# con-right-top.net
KiCad netlist of a schematic drawn in Altium Designer
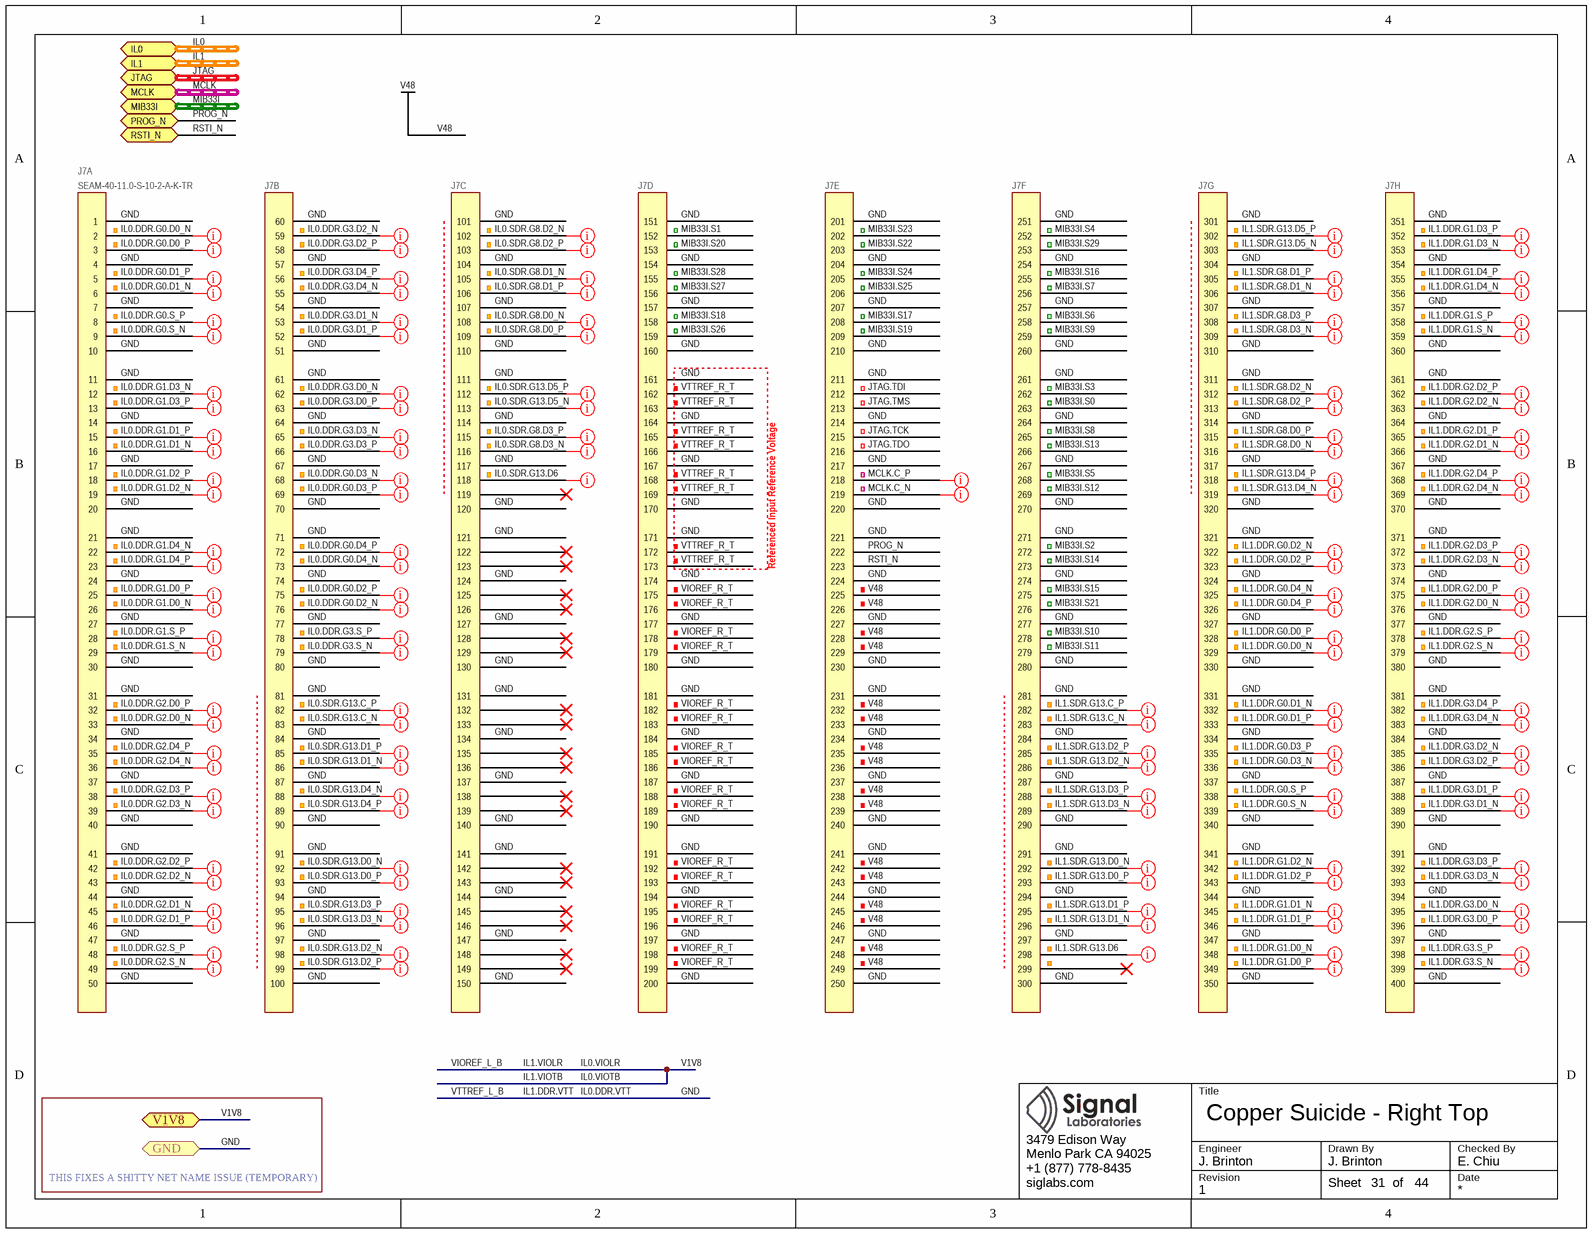
[diagram p0: con-right-top.SchDoc]

(export (version "E")
  (design (tool "Eeschema 10.0.6"))
  (components
    (comp (ref "J7")
      (value "SEAM-40-11.0-S-10-2-A-K-TR")
      (footprint "samtec:SEAM-40-11.0-S-10-2-A-K-TR")
      (description "Terminal Array Assembly, Surface Mount, 0.050\" Pitch, 400 Pins")
      (fields (field (name "MANUFACTURER") "Samtec"))
      (libsource (lib "samtec") (part "SEAM-40-11.0-S-10-2-A-K-TR"))
    )
  )
  (nets
    (net (code "6") (name "/GND") (class "Default")
      (node (ref "J7") (pin "1") (pinfunction "1_1") (pintype "passive"))
      (node (ref "J7") (pin "10") (pinfunction "10_10") (pintype "passive"))
      (node (ref "J7") (pin "100") (pinfunction "100_100") (pintype "passive"))
      (node (ref "J7") (pin "101") (pinfunction "101_101") (pintype "passive"))
      (node (ref "J7") (pin "104") (pinfunction "104_104") (pintype "passive"))
      (node (ref "J7") (pin "107") (pinfunction "107_107") (pintype "passive"))
      (node (ref "J7") (pin "11") (pinfunction "11_11") (pintype "passive"))
      (node (ref "J7") (pin "110") (pinfunction "110_110") (pintype "passive"))
      (node (ref "J7") (pin "111") (pinfunction "111_111") (pintype "passive"))
      (node (ref "J7") (pin "114") (pinfunction "114_114") (pintype "passive"))
      (node (ref "J7") (pin "117") (pinfunction "117_117") (pintype "passive"))
      (node (ref "J7") (pin "120") (pinfunction "120_120") (pintype "passive"))
      (node (ref "J7") (pin "121") (pinfunction "121_121") (pintype "passive"))
      (node (ref "J7") (pin "124") (pinfunction "124_124") (pintype "passive"))
      (node (ref "J7") (pin "127") (pinfunction "127_127") (pintype "passive"))
      (node (ref "J7") (pin "130") (pinfunction "130_130") (pintype "passive"))
      (node (ref "J7") (pin "131") (pinfunction "131_131") (pintype "passive"))
      (node (ref "J7") (pin "134") (pinfunction "134_134") (pintype "passive"))
      (node (ref "J7") (pin "137") (pinfunction "137_137") (pintype "passive"))
      (node (ref "J7") (pin "14") (pinfunction "14_14") (pintype "passive"))
      (node (ref "J7") (pin "140") (pinfunction "140_140") (pintype "passive"))
      (node (ref "J7") (pin "141") (pinfunction "141_141") (pintype "passive"))
      (node (ref "J7") (pin "144") (pinfunction "144_144") (pintype "passive"))
      (node (ref "J7") (pin "147") (pinfunction "147_147") (pintype "passive"))
      (node (ref "J7") (pin "150") (pinfunction "150_150") (pintype "passive"))
      (node (ref "J7") (pin "151") (pinfunction "151_151") (pintype "passive"))
      (node (ref "J7") (pin "154") (pinfunction "154_154") (pintype "passive"))
      (node (ref "J7") (pin "157") (pinfunction "157_157") (pintype "passive"))
      (node (ref "J7") (pin "160") (pinfunction "160_160") (pintype "passive"))
      (node (ref "J7") (pin "161") (pinfunction "161_161") (pintype "passive"))
      (node (ref "J7") (pin "164") (pinfunction "164_164") (pintype "passive"))
      (node (ref "J7") (pin "167") (pinfunction "167_167") (pintype "passive"))
      (node (ref "J7") (pin "17") (pinfunction "17_17") (pintype "passive"))
      (node (ref "J7") (pin "170") (pinfunction "170_170") (pintype "passive"))
      (node (ref "J7") (pin "171") (pinfunction "171_171") (pintype "passive"))
      (node (ref "J7") (pin "174") (pinfunction "174_174") (pintype "passive"))
      (node (ref "J7") (pin "177") (pinfunction "177_177") (pintype "passive"))
      (node (ref "J7") (pin "180") (pinfunction "180_180") (pintype "passive"))
      (node (ref "J7") (pin "181") (pinfunction "181_181") (pintype "passive"))
      (node (ref "J7") (pin "184") (pinfunction "184_184") (pintype "passive"))
      (node (ref "J7") (pin "187") (pinfunction "187_187") (pintype "passive"))
      (node (ref "J7") (pin "190") (pinfunction "190_190") (pintype "passive"))
      (node (ref "J7") (pin "191") (pinfunction "191_191") (pintype "passive"))
      (node (ref "J7") (pin "194") (pinfunction "194_194") (pintype "passive"))
      (node (ref "J7") (pin "197") (pinfunction "197_197") (pintype "passive"))
      (node (ref "J7") (pin "20") (pinfunction "20_20") (pintype "passive"))
      (node (ref "J7") (pin "200") (pinfunction "200_200") (pintype "passive"))
      (node (ref "J7") (pin "201") (pinfunction "201_201") (pintype "passive"))
      (node (ref "J7") (pin "204") (pinfunction "204_204") (pintype "passive"))
      (node (ref "J7") (pin "207") (pinfunction "207_207") (pintype "passive"))
      (node (ref "J7") (pin "21") (pinfunction "21_21") (pintype "passive"))
      (node (ref "J7") (pin "210") (pinfunction "210_210") (pintype "passive"))
      (node (ref "J7") (pin "211") (pinfunction "211_211") (pintype "passive"))
      (node (ref "J7") (pin "214") (pinfunction "214_214") (pintype "passive"))
      (node (ref "J7") (pin "217") (pinfunction "217_217") (pintype "passive"))
      (node (ref "J7") (pin "220") (pinfunction "220_220") (pintype "passive"))
      (node (ref "J7") (pin "221") (pinfunction "221_221") (pintype "passive"))
      (node (ref "J7") (pin "224") (pinfunction "224_224") (pintype "passive"))
      (node (ref "J7") (pin "227") (pinfunction "227_227") (pintype "passive"))
      (node (ref "J7") (pin "230") (pinfunction "230_230") (pintype "passive"))
      (node (ref "J7") (pin "231") (pinfunction "231_231") (pintype "passive"))
      (node (ref "J7") (pin "234") (pinfunction "234_234") (pintype "passive"))
      (node (ref "J7") (pin "237") (pinfunction "237_237") (pintype "passive"))
      (node (ref "J7") (pin "24") (pinfunction "24_24") (pintype "passive"))
      (node (ref "J7") (pin "240") (pinfunction "240_240") (pintype "passive"))
      (node (ref "J7") (pin "241") (pinfunction "241_241") (pintype "passive"))
      (node (ref "J7") (pin "244") (pinfunction "244_244") (pintype "passive"))
      (node (ref "J7") (pin "247") (pinfunction "247_247") (pintype "passive"))
      (node (ref "J7") (pin "250") (pinfunction "250_250") (pintype "passive"))
      (node (ref "J7") (pin "251") (pinfunction "251_251") (pintype "passive"))
      (node (ref "J7") (pin "254") (pinfunction "254_254") (pintype "passive"))
      (node (ref "J7") (pin "257") (pinfunction "257_257") (pintype "passive"))
      (node (ref "J7") (pin "260") (pinfunction "260_260") (pintype "passive"))
      (node (ref "J7") (pin "261") (pinfunction "261_261") (pintype "passive"))
      (node (ref "J7") (pin "264") (pinfunction "264_264") (pintype "passive"))
      (node (ref "J7") (pin "267") (pinfunction "267_267") (pintype "passive"))
      (node (ref "J7") (pin "27") (pinfunction "27_27") (pintype "passive"))
      (node (ref "J7") (pin "270") (pinfunction "270_270") (pintype "passive"))
      (node (ref "J7") (pin "271") (pinfunction "271_271") (pintype "passive"))
      (node (ref "J7") (pin "274") (pinfunction "274_274") (pintype "passive"))
      (node (ref "J7") (pin "277") (pinfunction "277_277") (pintype "passive"))
      (node (ref "J7") (pin "280") (pinfunction "280_280") (pintype "passive"))
      (node (ref "J7") (pin "281") (pinfunction "281_281") (pintype "passive"))
      (node (ref "J7") (pin "284") (pinfunction "284_284") (pintype "passive"))
      (node (ref "J7") (pin "287") (pinfunction "287_287") (pintype "passive"))
      (node (ref "J7") (pin "290") (pinfunction "290_290") (pintype "passive"))
      (node (ref "J7") (pin "291") (pinfunction "291_291") (pintype "passive"))
      (node (ref "J7") (pin "294") (pinfunction "294_294") (pintype "passive"))
      (node (ref "J7") (pin "297") (pinfunction "297_297") (pintype "passive"))
      (node (ref "J7") (pin "30") (pinfunction "30_30") (pintype "passive"))
      (node (ref "J7") (pin "300") (pinfunction "300_300") (pintype "passive"))
      (node (ref "J7") (pin "301") (pinfunction "301_301") (pintype "passive"))
      (node (ref "J7") (pin "304") (pinfunction "304_304") (pintype "passive"))
      (node (ref "J7") (pin "307") (pinfunction "307_307") (pintype "passive"))
      (node (ref "J7") (pin "31") (pinfunction "31_31") (pintype "passive"))
      (node (ref "J7") (pin "310") (pinfunction "310_310") (pintype "passive"))
      (node (ref "J7") (pin "311") (pinfunction "311_311") (pintype "passive"))
      (node (ref "J7") (pin "314") (pinfunction "314_314") (pintype "passive"))
      (node (ref "J7") (pin "317") (pinfunction "317_317") (pintype "passive"))
      (node (ref "J7") (pin "320") (pinfunction "320_320") (pintype "passive"))
      (node (ref "J7") (pin "321") (pinfunction "321_321") (pintype "passive"))
      (node (ref "J7") (pin "324") (pinfunction "324_324") (pintype "passive"))
      (node (ref "J7") (pin "327") (pinfunction "327_327") (pintype "passive"))
      (node (ref "J7") (pin "330") (pinfunction "330_330") (pintype "passive"))
      (node (ref "J7") (pin "331") (pinfunction "331_331") (pintype "passive"))
      (node (ref "J7") (pin "334") (pinfunction "334_334") (pintype "passive"))
      (node (ref "J7") (pin "337") (pinfunction "337_337") (pintype "passive"))
      (node (ref "J7") (pin "34") (pinfunction "34_34") (pintype "passive"))
      (node (ref "J7") (pin "340") (pinfunction "340_340") (pintype "passive"))
      (node (ref "J7") (pin "341") (pinfunction "341_341") (pintype "passive"))
      (node (ref "J7") (pin "344") (pinfunction "344_344") (pintype "passive"))
      (node (ref "J7") (pin "347") (pinfunction "347_347") (pintype "passive"))
      (node (ref "J7") (pin "350") (pinfunction "350_350") (pintype "passive"))
      (node (ref "J7") (pin "351") (pinfunction "351_351") (pintype "passive"))
      (node (ref "J7") (pin "354") (pinfunction "354_354") (pintype "passive"))
      (node (ref "J7") (pin "357") (pinfunction "357_357") (pintype "passive"))
      (node (ref "J7") (pin "360") (pinfunction "360_360") (pintype "passive"))
      (node (ref "J7") (pin "361") (pinfunction "361_361") (pintype "passive"))
      (node (ref "J7") (pin "364") (pinfunction "364_364") (pintype "passive"))
      (node (ref "J7") (pin "367") (pinfunction "367_367") (pintype "passive"))
      (node (ref "J7") (pin "37") (pinfunction "37_37") (pintype "passive"))
      (node (ref "J7") (pin "370") (pinfunction "370_370") (pintype "passive"))
      (node (ref "J7") (pin "371") (pinfunction "371_371") (pintype "passive"))
      (node (ref "J7") (pin "374") (pinfunction "374_374") (pintype "passive"))
      (node (ref "J7") (pin "377") (pinfunction "377_377") (pintype "passive"))
      (node (ref "J7") (pin "380") (pinfunction "380_380") (pintype "passive"))
      (node (ref "J7") (pin "381") (pinfunction "381_381") (pintype "passive"))
      (node (ref "J7") (pin "384") (pinfunction "384_384") (pintype "passive"))
      (node (ref "J7") (pin "387") (pinfunction "387_387") (pintype "passive"))
      (node (ref "J7") (pin "390") (pinfunction "390_390") (pintype "passive"))
      (node (ref "J7") (pin "391") (pinfunction "391_391") (pintype "passive"))
      (node (ref "J7") (pin "394") (pinfunction "394_394") (pintype "passive"))
      (node (ref "J7") (pin "397") (pinfunction "397_397") (pintype "passive"))
      (node (ref "J7") (pin "4") (pinfunction "4_4") (pintype "passive"))
      (node (ref "J7") (pin "40") (pinfunction "40_40") (pintype "passive"))
      (node (ref "J7") (pin "400") (pinfunction "400_400") (pintype "passive"))
      (node (ref "J7") (pin "41") (pinfunction "41_41") (pintype "passive"))
      (node (ref "J7") (pin "44") (pinfunction "44_44") (pintype "passive"))
      (node (ref "J7") (pin "47") (pinfunction "47_47") (pintype "passive"))
      (node (ref "J7") (pin "50") (pinfunction "50_50") (pintype "passive"))
      (node (ref "J7") (pin "51") (pinfunction "51_51") (pintype "passive"))
      (node (ref "J7") (pin "54") (pinfunction "54_54") (pintype "passive"))
      (node (ref "J7") (pin "57") (pinfunction "57_57") (pintype "passive"))
      (node (ref "J7") (pin "60") (pinfunction "60_60") (pintype "passive"))
      (node (ref "J7") (pin "61") (pinfunction "61_61") (pintype "passive"))
      (node (ref "J7") (pin "64") (pinfunction "64_64") (pintype "passive"))
      (node (ref "J7") (pin "67") (pinfunction "67_67") (pintype "passive"))
      (node (ref "J7") (pin "7") (pinfunction "7_7") (pintype "passive"))
      (node (ref "J7") (pin "70") (pinfunction "70_70") (pintype "passive"))
      (node (ref "J7") (pin "71") (pinfunction "71_71") (pintype "passive"))
      (node (ref "J7") (pin "74") (pinfunction "74_74") (pintype "passive"))
      (node (ref "J7") (pin "77") (pinfunction "77_77") (pintype "passive"))
      (node (ref "J7") (pin "80") (pinfunction "80_80") (pintype "passive"))
      (node (ref "J7") (pin "81") (pinfunction "81_81") (pintype "passive"))
      (node (ref "J7") (pin "84") (pinfunction "84_84") (pintype "passive"))
      (node (ref "J7") (pin "87") (pinfunction "87_87") (pintype "passive"))
      (node (ref "J7") (pin "90") (pinfunction "90_90") (pintype "passive"))
      (node (ref "J7") (pin "91") (pinfunction "91_91") (pintype "passive"))
      (node (ref "J7") (pin "94") (pinfunction "94_94") (pintype "passive"))
      (node (ref "J7") (pin "97") (pinfunction "97_97") (pintype "passive"))
    )
    (net (code "7") (name "/IL0.DDR.G0.D0_N") (class "Default")
      (node (ref "J7") (pin "2") (pinfunction "2_2") (pintype "passive"))
    )
    (net (code "8") (name "/IL0.DDR.G0.D0_P") (class "Default")
      (node (ref "J7") (pin "3") (pinfunction "3_3") (pintype "passive"))
    )
    (net (code "9") (name "/IL0.DDR.G0.D1_N") (class "Default")
      (node (ref "J7") (pin "6") (pinfunction "6_6") (pintype "passive"))
    )
    (net (code "10") (name "/IL0.DDR.G0.D1_P") (class "Default")
      (node (ref "J7") (pin "5") (pinfunction "5_5") (pintype "passive"))
    )
    (net (code "11") (name "/IL0.DDR.G0.D2_N") (class "Default")
      (node (ref "J7") (pin "76") (pinfunction "76_76") (pintype "passive"))
    )
    (net (code "12") (name "/IL0.DDR.G0.D2_P") (class "Default")
      (node (ref "J7") (pin "75") (pinfunction "75_75") (pintype "passive"))
    )
    (net (code "13") (name "/IL0.DDR.G0.D3_N") (class "Default")
      (node (ref "J7") (pin "68") (pinfunction "68_68") (pintype "passive"))
    )
    (net (code "14") (name "/IL0.DDR.G0.D3_P") (class "Default")
      (node (ref "J7") (pin "69") (pinfunction "69_69") (pintype "passive"))
    )
    (net (code "15") (name "/IL0.DDR.G0.D4_N") (class "Default")
      (node (ref "J7") (pin "73") (pinfunction "73_73") (pintype "passive"))
    )
    (net (code "16") (name "/IL0.DDR.G0.D4_P") (class "Default")
      (node (ref "J7") (pin "72") (pinfunction "72_72") (pintype "passive"))
    )
    (net (code "17") (name "/IL0.DDR.G0.S_N") (class "Default")
      (node (ref "J7") (pin "9") (pinfunction "9_9") (pintype "passive"))
    )
    (net (code "18") (name "/IL0.DDR.G0.S_P") (class "Default")
      (node (ref "J7") (pin "8") (pinfunction "8_8") (pintype "passive"))
    )
    (net (code "19") (name "/IL0.DDR.G1.D0_N") (class "Default")
      (node (ref "J7") (pin "26") (pinfunction "26_26") (pintype "passive"))
    )
    (net (code "20") (name "/IL0.DDR.G1.D0_P") (class "Default")
      (node (ref "J7") (pin "25") (pinfunction "25_25") (pintype "passive"))
    )
    (net (code "21") (name "/IL0.DDR.G1.D1_N") (class "Default")
      (node (ref "J7") (pin "16") (pinfunction "16_16") (pintype "passive"))
    )
    (net (code "22") (name "/IL0.DDR.G1.D1_P") (class "Default")
      (node (ref "J7") (pin "15") (pinfunction "15_15") (pintype "passive"))
    )
    (net (code "23") (name "/IL0.DDR.G1.D2_N") (class "Default")
      (node (ref "J7") (pin "19") (pinfunction "19_19") (pintype "passive"))
    )
    (net (code "24") (name "/IL0.DDR.G1.D2_P") (class "Default")
      (node (ref "J7") (pin "18") (pinfunction "18_18") (pintype "passive"))
    )
    (net (code "25") (name "/IL0.DDR.G1.D3_N") (class "Default")
      (node (ref "J7") (pin "12") (pinfunction "12_12") (pintype "passive"))
    )
    (net (code "26") (name "/IL0.DDR.G1.D3_P") (class "Default")
      (node (ref "J7") (pin "13") (pinfunction "13_13") (pintype "passive"))
    )
    (net (code "27") (name "/IL0.DDR.G1.D4_N") (class "Default")
      (node (ref "J7") (pin "22") (pinfunction "22_22") (pintype "passive"))
    )
    (net (code "28") (name "/IL0.DDR.G1.D4_P") (class "Default")
      (node (ref "J7") (pin "23") (pinfunction "23_23") (pintype "passive"))
    )
    (net (code "29") (name "/IL0.DDR.G1.S_N") (class "Default")
      (node (ref "J7") (pin "29") (pinfunction "29_29") (pintype "passive"))
    )
    (net (code "30") (name "/IL0.DDR.G1.S_P") (class "Default")
      (node (ref "J7") (pin "28") (pinfunction "28_28") (pintype "passive"))
    )
    (net (code "31") (name "/IL0.DDR.G2.D0_N") (class "Default")
      (node (ref "J7") (pin "33") (pinfunction "33_33") (pintype "passive"))
    )
    (net (code "32") (name "/IL0.DDR.G2.D0_P") (class "Default")
      (node (ref "J7") (pin "32") (pinfunction "32_32") (pintype "passive"))
    )
    (net (code "33") (name "/IL0.DDR.G2.D1_N") (class "Default")
      (node (ref "J7") (pin "45") (pinfunction "45_45") (pintype "passive"))
    )
    (net (code "34") (name "/IL0.DDR.G2.D1_P") (class "Default")
      (node (ref "J7") (pin "46") (pinfunction "46_46") (pintype "passive"))
    )
    (net (code "35") (name "/IL0.DDR.G2.D2_N") (class "Default")
      (node (ref "J7") (pin "43") (pinfunction "43_43") (pintype "passive"))
    )
    (net (code "36") (name "/IL0.DDR.G2.D2_P") (class "Default")
      (node (ref "J7") (pin "42") (pinfunction "42_42") (pintype "passive"))
    )
    (net (code "37") (name "/IL0.DDR.G2.D3_N") (class "Default")
      (node (ref "J7") (pin "39") (pinfunction "39_39") (pintype "passive"))
    )
    (net (code "38") (name "/IL0.DDR.G2.D3_P") (class "Default")
      (node (ref "J7") (pin "38") (pinfunction "38_38") (pintype "passive"))
    )
    (net (code "39") (name "/IL0.DDR.G2.D4_N") (class "Default")
      (node (ref "J7") (pin "36") (pinfunction "36_36") (pintype "passive"))
    )
    (net (code "40") (name "/IL0.DDR.G2.D4_P") (class "Default")
      (node (ref "J7") (pin "35") (pinfunction "35_35") (pintype "passive"))
    )
    (net (code "41") (name "/IL0.DDR.G2.S_N") (class "Default")
      (node (ref "J7") (pin "49") (pinfunction "49_49") (pintype "passive"))
    )
    (net (code "42") (name "/IL0.DDR.G2.S_P") (class "Default")
      (node (ref "J7") (pin "48") (pinfunction "48_48") (pintype "passive"))
    )
    (net (code "43") (name "/IL0.DDR.G3.D0_N") (class "Default")
      (node (ref "J7") (pin "62") (pinfunction "62_62") (pintype "passive"))
    )
    (net (code "44") (name "/IL0.DDR.G3.D0_P") (class "Default")
      (node (ref "J7") (pin "63") (pinfunction "63_63") (pintype "passive"))
    )
    (net (code "45") (name "/IL0.DDR.G3.D1_N") (class "Default")
      (node (ref "J7") (pin "53") (pinfunction "53_53") (pintype "passive"))
    )
    (net (code "46") (name "/IL0.DDR.G3.D1_P") (class "Default")
      (node (ref "J7") (pin "52") (pinfunction "52_52") (pintype "passive"))
    )
    (net (code "47") (name "/IL0.DDR.G3.D2_N") (class "Default")
      (node (ref "J7") (pin "59") (pinfunction "59_59") (pintype "passive"))
    )
    (net (code "48") (name "/IL0.DDR.G3.D2_P") (class "Default")
      (node (ref "J7") (pin "58") (pinfunction "58_58") (pintype "passive"))
    )
    (net (code "49") (name "/IL0.DDR.G3.D3_N") (class "Default")
      (node (ref "J7") (pin "65") (pinfunction "65_65") (pintype "passive"))
    )
    (net (code "50") (name "/IL0.DDR.G3.D3_P") (class "Default")
      (node (ref "J7") (pin "66") (pinfunction "66_66") (pintype "passive"))
    )
    (net (code "51") (name "/IL0.DDR.G3.D4_N") (class "Default")
      (node (ref "J7") (pin "55") (pinfunction "55_55") (pintype "passive"))
    )
    (net (code "52") (name "/IL0.DDR.G3.D4_P") (class "Default")
      (node (ref "J7") (pin "56") (pinfunction "56_56") (pintype "passive"))
    )
    (net (code "53") (name "/IL0.DDR.G3.S_N") (class "Default")
      (node (ref "J7") (pin "79") (pinfunction "79_79") (pintype "passive"))
    )
    (net (code "54") (name "/IL0.DDR.G3.S_P") (class "Default")
      (node (ref "J7") (pin "78") (pinfunction "78_78") (pintype "passive"))
    )
    (net (code "55") (name "/IL0.SDR.G8.D0_N") (class "Default")
      (node (ref "J7") (pin "108") (pinfunction "108_108") (pintype "passive"))
    )
    (net (code "56") (name "/IL0.SDR.G8.D0_P") (class "Default")
      (node (ref "J7") (pin "109") (pinfunction "109_109") (pintype "passive"))
    )
    (net (code "57") (name "/IL0.SDR.G8.D1_N") (class "Default")
      (node (ref "J7") (pin "105") (pinfunction "105_105") (pintype "passive"))
    )
    (net (code "58") (name "/IL0.SDR.G8.D1_P") (class "Default")
      (node (ref "J7") (pin "106") (pinfunction "106_106") (pintype "passive"))
    )
    (net (code "59") (name "/IL0.SDR.G8.D2_N") (class "Default")
      (node (ref "J7") (pin "102") (pinfunction "102_102") (pintype "passive"))
    )
    (net (code "60") (name "/IL0.SDR.G8.D2_P") (class "Default")
      (node (ref "J7") (pin "103") (pinfunction "103_103") (pintype "passive"))
    )
    (net (code "61") (name "/IL0.SDR.G8.D3_N") (class "Default")
      (node (ref "J7") (pin "116") (pinfunction "116_116") (pintype "passive"))
    )
    (net (code "62") (name "/IL0.SDR.G8.D3_P") (class "Default")
      (node (ref "J7") (pin "115") (pinfunction "115_115") (pintype "passive"))
    )
    (net (code "63") (name "/IL0.SDR.G13.C_N") (class "Default")
      (node (ref "J7") (pin "83") (pinfunction "83_83") (pintype "passive"))
    )
    (net (code "64") (name "/IL0.SDR.G13.C_P") (class "Default")
      (node (ref "J7") (pin "82") (pinfunction "82_82") (pintype "passive"))
    )
    (net (code "65") (name "/IL0.SDR.G13.D0_N") (class "Default")
      (node (ref "J7") (pin "92") (pinfunction "92_92") (pintype "passive"))
    )
    (net (code "66") (name "/IL0.SDR.G13.D0_P") (class "Default")
      (node (ref "J7") (pin "93") (pinfunction "93_93") (pintype "passive"))
    )
    (net (code "67") (name "/IL0.SDR.G13.D1_N") (class "Default")
      (node (ref "J7") (pin "86") (pinfunction "86_86") (pintype "passive"))
    )
    (net (code "68") (name "/IL0.SDR.G13.D1_P") (class "Default")
      (node (ref "J7") (pin "85") (pinfunction "85_85") (pintype "passive"))
    )
    (net (code "69") (name "/IL0.SDR.G13.D2_N") (class "Default")
      (node (ref "J7") (pin "98") (pinfunction "98_98") (pintype "passive"))
    )
    (net (code "70") (name "/IL0.SDR.G13.D2_P") (class "Default")
      (node (ref "J7") (pin "99") (pinfunction "99_99") (pintype "passive"))
    )
    (net (code "71") (name "/IL0.SDR.G13.D3_N") (class "Default")
      (node (ref "J7") (pin "96") (pinfunction "96_96") (pintype "passive"))
    )
    (net (code "72") (name "/IL0.SDR.G13.D3_P") (class "Default")
      (node (ref "J7") (pin "95") (pinfunction "95_95") (pintype "passive"))
    )
    (net (code "73") (name "/IL0.SDR.G13.D4_N") (class "Default")
      (node (ref "J7") (pin "88") (pinfunction "88_88") (pintype "passive"))
    )
    (net (code "74") (name "/IL0.SDR.G13.D4_P") (class "Default")
      (node (ref "J7") (pin "89") (pinfunction "89_89") (pintype "passive"))
    )
    (net (code "75") (name "/IL0.SDR.G13.D5_N") (class "Default")
      (node (ref "J7") (pin "113") (pinfunction "113_113") (pintype "passive"))
    )
    (net (code "76") (name "/IL0.SDR.G13.D5_P") (class "Default")
      (node (ref "J7") (pin "112") (pinfunction "112_112") (pintype "passive"))
    )
    (net (code "77") (name "/IL0.SDR.G13.D6") (class "Default")
      (node (ref "J7") (pin "118") (pinfunction "118_118") (pintype "passive"))
    )
    (net (code "79") (name "/IL1.DDR.G0.D0_N") (class "Default")
      (node (ref "J7") (pin "329") (pinfunction "329_329") (pintype "passive"))
    )
    (net (code "80") (name "/IL1.DDR.G0.D0_P") (class "Default")
      (node (ref "J7") (pin "328") (pinfunction "328_328") (pintype "passive"))
    )
    (net (code "81") (name "/IL1.DDR.G0.D1_N") (class "Default")
      (node (ref "J7") (pin "332") (pinfunction "332_332") (pintype "passive"))
    )
    (net (code "82") (name "/IL1.DDR.G0.D1_P") (class "Default")
      (node (ref "J7") (pin "333") (pinfunction "333_333") (pintype "passive"))
    )
    (net (code "83") (name "/IL1.DDR.G0.D2_N") (class "Default")
      (node (ref "J7") (pin "322") (pinfunction "322_322") (pintype "passive"))
    )
    (net (code "84") (name "/IL1.DDR.G0.D2_P") (class "Default")
      (node (ref "J7") (pin "323") (pinfunction "323_323") (pintype "passive"))
    )
    (net (code "85") (name "/IL1.DDR.G0.D3_N") (class "Default")
      (node (ref "J7") (pin "336") (pinfunction "336_336") (pintype "passive"))
    )
    (net (code "86") (name "/IL1.DDR.G0.D3_P") (class "Default")
      (node (ref "J7") (pin "335") (pinfunction "335_335") (pintype "passive"))
    )
    (net (code "87") (name "/IL1.DDR.G0.D4_N") (class "Default")
      (node (ref "J7") (pin "325") (pinfunction "325_325") (pintype "passive"))
    )
    (net (code "88") (name "/IL1.DDR.G0.D4_P") (class "Default")
      (node (ref "J7") (pin "326") (pinfunction "326_326") (pintype "passive"))
    )
    (net (code "89") (name "/IL1.DDR.G0.S_N") (class "Default")
      (node (ref "J7") (pin "339") (pinfunction "339_339") (pintype "passive"))
    )
    (net (code "90") (name "/IL1.DDR.G0.S_P") (class "Default")
      (node (ref "J7") (pin "338") (pinfunction "338_338") (pintype "passive"))
    )
    (net (code "91") (name "/IL1.DDR.G1.D0_N") (class "Default")
      (node (ref "J7") (pin "348") (pinfunction "348_348") (pintype "passive"))
    )
    (net (code "92") (name "/IL1.DDR.G1.D0_P") (class "Default")
      (node (ref "J7") (pin "349") (pinfunction "349_349") (pintype "passive"))
    )
    (net (code "93") (name "/IL1.DDR.G1.D1_N") (class "Default")
      (node (ref "J7") (pin "345") (pinfunction "345_345") (pintype "passive"))
    )
    (net (code "94") (name "/IL1.DDR.G1.D1_P") (class "Default")
      (node (ref "J7") (pin "346") (pinfunction "346_346") (pintype "passive"))
    )
    (net (code "95") (name "/IL1.DDR.G1.D2_N") (class "Default")
      (node (ref "J7") (pin "342") (pinfunction "342_342") (pintype "passive"))
    )
    (net (code "96") (name "/IL1.DDR.G1.D2_P") (class "Default")
      (node (ref "J7") (pin "343") (pinfunction "343_343") (pintype "passive"))
    )
    (net (code "97") (name "/IL1.DDR.G1.D3_N") (class "Default")
      (node (ref "J7") (pin "353") (pinfunction "353_353") (pintype "passive"))
    )
    (net (code "98") (name "/IL1.DDR.G1.D3_P") (class "Default")
      (node (ref "J7") (pin "352") (pinfunction "352_352") (pintype "passive"))
    )
    (net (code "99") (name "/IL1.DDR.G1.D4_N") (class "Default")
      (node (ref "J7") (pin "356") (pinfunction "356_356") (pintype "passive"))
    )
    (net (code "100") (name "/IL1.DDR.G1.D4_P") (class "Default")
      (node (ref "J7") (pin "355") (pinfunction "355_355") (pintype "passive"))
    )
    (net (code "101") (name "/IL1.DDR.G1.S_N") (class "Default")
      (node (ref "J7") (pin "359") (pinfunction "359_359") (pintype "passive"))
    )
    (net (code "102") (name "/IL1.DDR.G1.S_P") (class "Default")
      (node (ref "J7") (pin "358") (pinfunction "358_358") (pintype "passive"))
    )
    (net (code "103") (name "/IL1.DDR.G2.D0_N") (class "Default")
      (node (ref "J7") (pin "376") (pinfunction "376_376") (pintype "passive"))
    )
    (net (code "104") (name "/IL1.DDR.G2.D0_P") (class "Default")
      (node (ref "J7") (pin "375") (pinfunction "375_375") (pintype "passive"))
    )
    (net (code "105") (name "/IL1.DDR.G2.D1_N") (class "Default")
      (node (ref "J7") (pin "366") (pinfunction "366_366") (pintype "passive"))
    )
    (net (code "106") (name "/IL1.DDR.G2.D1_P") (class "Default")
      (node (ref "J7") (pin "365") (pinfunction "365_365") (pintype "passive"))
    )
    (net (code "107") (name "/IL1.DDR.G2.D2_N") (class "Default")
      (node (ref "J7") (pin "363") (pinfunction "363_363") (pintype "passive"))
    )
    (net (code "108") (name "/IL1.DDR.G2.D2_P") (class "Default")
      (node (ref "J7") (pin "362") (pinfunction "362_362") (pintype "passive"))
    )
    (net (code "109") (name "/IL1.DDR.G2.D3_N") (class "Default")
      (node (ref "J7") (pin "373") (pinfunction "373_373") (pintype "passive"))
    )
    (net (code "110") (name "/IL1.DDR.G2.D3_P") (class "Default")
      (node (ref "J7") (pin "372") (pinfunction "372_372") (pintype "passive"))
    )
    (net (code "111") (name "/IL1.DDR.G2.D4_N") (class "Default")
      (node (ref "J7") (pin "369") (pinfunction "369_369") (pintype "passive"))
    )
    (net (code "112") (name "/IL1.DDR.G2.D4_P") (class "Default")
      (node (ref "J7") (pin "368") (pinfunction "368_368") (pintype "passive"))
    )
    (net (code "113") (name "/IL1.DDR.G2.S_N") (class "Default")
      (node (ref "J7") (pin "379") (pinfunction "379_379") (pintype "passive"))
    )
    (net (code "114") (name "/IL1.DDR.G2.S_P") (class "Default")
      (node (ref "J7") (pin "378") (pinfunction "378_378") (pintype "passive"))
    )
    (net (code "115") (name "/IL1.DDR.G3.D0_N") (class "Default")
      (node (ref "J7") (pin "395") (pinfunction "395_395") (pintype "passive"))
    )
    (net (code "116") (name "/IL1.DDR.G3.D0_P") (class "Default")
      (node (ref "J7") (pin "396") (pinfunction "396_396") (pintype "passive"))
    )
    (net (code "117") (name "/IL1.DDR.G3.D1_N") (class "Default")
      (node (ref "J7") (pin "389") (pinfunction "389_389") (pintype "passive"))
    )
    (net (code "118") (name "/IL1.DDR.G3.D1_P") (class "Default")
      (node (ref "J7") (pin "388") (pinfunction "388_388") (pintype "passive"))
    )
    (net (code "119") (name "/IL1.DDR.G3.D2_N") (class "Default")
      (node (ref "J7") (pin "385") (pinfunction "385_385") (pintype "passive"))
    )
    (net (code "120") (name "/IL1.DDR.G3.D2_P") (class "Default")
      (node (ref "J7") (pin "386") (pinfunction "386_386") (pintype "passive"))
    )
    (net (code "121") (name "/IL1.DDR.G3.D3_N") (class "Default")
      (node (ref "J7") (pin "393") (pinfunction "393_393") (pintype "passive"))
    )
    (net (code "122") (name "/IL1.DDR.G3.D3_P") (class "Default")
      (node (ref "J7") (pin "392") (pinfunction "392_392") (pintype "passive"))
    )
    (net (code "123") (name "/IL1.DDR.G3.D4_N") (class "Default")
      (node (ref "J7") (pin "383") (pinfunction "383_383") (pintype "passive"))
    )
    (net (code "124") (name "/IL1.DDR.G3.D4_P") (class "Default")
      (node (ref "J7") (pin "382") (pinfunction "382_382") (pintype "passive"))
    )
    (net (code "125") (name "/IL1.DDR.G3.S_N") (class "Default")
      (node (ref "J7") (pin "399") (pinfunction "399_399") (pintype "passive"))
    )
    (net (code "126") (name "/IL1.DDR.G3.S_P") (class "Default")
      (node (ref "J7") (pin "398") (pinfunction "398_398") (pintype "passive"))
    )
    (net (code "127") (name "/IL1.SDR.G8.D0_N") (class "Default")
      (node (ref "J7") (pin "316") (pinfunction "316_316") (pintype "passive"))
    )
    (net (code "128") (name "/IL1.SDR.G8.D0_P") (class "Default")
      (node (ref "J7") (pin "315") (pinfunction "315_315") (pintype "passive"))
    )
    (net (code "129") (name "/IL1.SDR.G8.D1_N") (class "Default")
      (node (ref "J7") (pin "306") (pinfunction "306_306") (pintype "passive"))
    )
    (net (code "130") (name "/IL1.SDR.G8.D1_P") (class "Default")
      (node (ref "J7") (pin "305") (pinfunction "305_305") (pintype "passive"))
    )
    (net (code "131") (name "/IL1.SDR.G8.D2_N") (class "Default")
      (node (ref "J7") (pin "312") (pinfunction "312_312") (pintype "passive"))
    )
    (net (code "132") (name "/IL1.SDR.G8.D2_P") (class "Default")
      (node (ref "J7") (pin "313") (pinfunction "313_313") (pintype "passive"))
    )
    (net (code "133") (name "/IL1.SDR.G8.D3_N") (class "Default")
      (node (ref "J7") (pin "309") (pinfunction "309_309") (pintype "passive"))
    )
    (net (code "134") (name "/IL1.SDR.G8.D3_P") (class "Default")
      (node (ref "J7") (pin "308") (pinfunction "308_308") (pintype "passive"))
    )
    (net (code "135") (name "/IL1.SDR.G13.C_N") (class "Default")
      (node (ref "J7") (pin "283") (pinfunction "283_283") (pintype "passive"))
    )
    (net (code "136") (name "/IL1.SDR.G13.C_P") (class "Default")
      (node (ref "J7") (pin "282") (pinfunction "282_282") (pintype "passive"))
    )
    (net (code "137") (name "/IL1.SDR.G13.D0_N") (class "Default")
      (node (ref "J7") (pin "292") (pinfunction "292_292") (pintype "passive"))
    )
    (net (code "138") (name "/IL1.SDR.G13.D0_P") (class "Default")
      (node (ref "J7") (pin "293") (pinfunction "293_293") (pintype "passive"))
    )
    (net (code "139") (name "/IL1.SDR.G13.D1_N") (class "Default")
      (node (ref "J7") (pin "296") (pinfunction "296_296") (pintype "passive"))
    )
    (net (code "140") (name "/IL1.SDR.G13.D1_P") (class "Default")
      (node (ref "J7") (pin "295") (pinfunction "295_295") (pintype "passive"))
    )
    (net (code "141") (name "/IL1.SDR.G13.D2_N") (class "Default")
      (node (ref "J7") (pin "286") (pinfunction "286_286") (pintype "passive"))
    )
    (net (code "142") (name "/IL1.SDR.G13.D2_P") (class "Default")
      (node (ref "J7") (pin "285") (pinfunction "285_285") (pintype "passive"))
    )
    (net (code "143") (name "/IL1.SDR.G13.D3_N") (class "Default")
      (node (ref "J7") (pin "289") (pinfunction "289_289") (pintype "passive"))
    )
    (net (code "144") (name "/IL1.SDR.G13.D3_P") (class "Default")
      (node (ref "J7") (pin "288") (pinfunction "288_288") (pintype "passive"))
    )
    (net (code "145") (name "/IL1.SDR.G13.D4_N") (class "Default")
      (node (ref "J7") (pin "319") (pinfunction "319_319") (pintype "passive"))
    )
    (net (code "146") (name "/IL1.SDR.G13.D4_P") (class "Default")
      (node (ref "J7") (pin "318") (pinfunction "318_318") (pintype "passive"))
    )
    (net (code "147") (name "/IL1.SDR.G13.D5_N") (class "Default")
      (node (ref "J7") (pin "303") (pinfunction "303_303") (pintype "passive"))
    )
    (net (code "148") (name "/IL1.SDR.G13.D5_P") (class "Default")
      (node (ref "J7") (pin "302") (pinfunction "302_302") (pintype "passive"))
    )
    (net (code "149") (name "/IL1.SDR.G13.D6") (class "Default")
      (node (ref "J7") (pin "298") (pinfunction "298_298") (pintype "passive"))
    )
    (net (code "150") (name "/JTAG.TCK") (class "Default")
      (node (ref "J7") (pin "215") (pinfunction "215_215") (pintype "passive"))
    )
    (net (code "151") (name "/JTAG.TDI") (class "Default")
      (node (ref "J7") (pin "212") (pinfunction "212_212") (pintype "passive"))
    )
    (net (code "152") (name "/JTAG.TDO") (class "Default")
      (node (ref "J7") (pin "216") (pinfunction "216_216") (pintype "passive"))
    )
    (net (code "153") (name "/JTAG.TMS") (class "Default")
      (node (ref "J7") (pin "213") (pinfunction "213_213") (pintype "passive"))
    )
    (net (code "154") (name "/MCLK.C_N") (class "Default")
      (node (ref "J7") (pin "219") (pinfunction "219_219") (pintype "passive"))
    )
    (net (code "155") (name "/MCLK.C_P") (class "Default")
      (node (ref "J7") (pin "218") (pinfunction "218_218") (pintype "passive"))
    )
    (net (code "156") (name "/MIB33I.S0") (class "Default")
      (node (ref "J7") (pin "263") (pinfunction "263_263") (pintype "passive"))
    )
    (net (code "157") (name "/MIB33I.S1") (class "Default")
      (node (ref "J7") (pin "152") (pinfunction "152_152") (pintype "passive"))
    )
    (net (code "158") (name "/MIB33I.S2") (class "Default")
      (node (ref "J7") (pin "272") (pinfunction "272_272") (pintype "passive"))
    )
    (net (code "159") (name "/MIB33I.S3") (class "Default")
      (node (ref "J7") (pin "262") (pinfunction "262_262") (pintype "passive"))
    )
    (net (code "160") (name "/MIB33I.S4") (class "Default")
      (node (ref "J7") (pin "252") (pinfunction "252_252") (pintype "passive"))
    )
    (net (code "161") (name "/MIB33I.S5") (class "Default")
      (node (ref "J7") (pin "268") (pinfunction "268_268") (pintype "passive"))
    )
    (net (code "162") (name "/MIB33I.S6") (class "Default")
      (node (ref "J7") (pin "258") (pinfunction "258_258") (pintype "passive"))
    )
    (net (code "163") (name "/MIB33I.S7") (class "Default")
      (node (ref "J7") (pin "256") (pinfunction "256_256") (pintype "passive"))
    )
    (net (code "164") (name "/MIB33I.S8") (class "Default")
      (node (ref "J7") (pin "265") (pinfunction "265_265") (pintype "passive"))
    )
    (net (code "165") (name "/MIB33I.S9") (class "Default")
      (node (ref "J7") (pin "259") (pinfunction "259_259") (pintype "passive"))
    )
    (net (code "166") (name "/MIB33I.S10") (class "Default")
      (node (ref "J7") (pin "278") (pinfunction "278_278") (pintype "passive"))
    )
    (net (code "167") (name "/MIB33I.S11") (class "Default")
      (node (ref "J7") (pin "279") (pinfunction "279_279") (pintype "passive"))
    )
    (net (code "168") (name "/MIB33I.S12") (class "Default")
      (node (ref "J7") (pin "269") (pinfunction "269_269") (pintype "passive"))
    )
    (net (code "169") (name "/MIB33I.S13") (class "Default")
      (node (ref "J7") (pin "266") (pinfunction "266_266") (pintype "passive"))
    )
    (net (code "170") (name "/MIB33I.S14") (class "Default")
      (node (ref "J7") (pin "273") (pinfunction "273_273") (pintype "passive"))
    )
    (net (code "171") (name "/MIB33I.S15") (class "Default")
      (node (ref "J7") (pin "275") (pinfunction "275_275") (pintype "passive"))
    )
    (net (code "172") (name "/MIB33I.S16") (class "Default")
      (node (ref "J7") (pin "255") (pinfunction "255_255") (pintype "passive"))
    )
    (net (code "173") (name "/MIB33I.S17") (class "Default")
      (node (ref "J7") (pin "208") (pinfunction "208_208") (pintype "passive"))
    )
    (net (code "174") (name "/MIB33I.S18") (class "Default")
      (node (ref "J7") (pin "158") (pinfunction "158_158") (pintype "passive"))
    )
    (net (code "175") (name "/MIB33I.S19") (class "Default")
      (node (ref "J7") (pin "209") (pinfunction "209_209") (pintype "passive"))
    )
    (net (code "176") (name "/MIB33I.S20") (class "Default")
      (node (ref "J7") (pin "153") (pinfunction "153_153") (pintype "passive"))
    )
    (net (code "177") (name "/MIB33I.S21") (class "Default")
      (node (ref "J7") (pin "276") (pinfunction "276_276") (pintype "passive"))
    )
    (net (code "178") (name "/MIB33I.S22") (class "Default")
      (node (ref "J7") (pin "203") (pinfunction "203_203") (pintype "passive"))
    )
    (net (code "179") (name "/MIB33I.S23") (class "Default")
      (node (ref "J7") (pin "202") (pinfunction "202_202") (pintype "passive"))
    )
    (net (code "180") (name "/MIB33I.S24") (class "Default")
      (node (ref "J7") (pin "205") (pinfunction "205_205") (pintype "passive"))
    )
    (net (code "181") (name "/MIB33I.S25") (class "Default")
      (node (ref "J7") (pin "206") (pinfunction "206_206") (pintype "passive"))
    )
    (net (code "182") (name "/MIB33I.S26") (class "Default")
      (node (ref "J7") (pin "159") (pinfunction "159_159") (pintype "passive"))
    )
    (net (code "183") (name "/MIB33I.S27") (class "Default")
      (node (ref "J7") (pin "156") (pinfunction "156_156") (pintype "passive"))
    )
    (net (code "184") (name "/MIB33I.S28") (class "Default")
      (node (ref "J7") (pin "155") (pinfunction "155_155") (pintype "passive"))
    )
    (net (code "185") (name "/MIB33I.S29") (class "Default")
      (node (ref "J7") (pin "253") (pinfunction "253_253") (pintype "passive"))
    )
    (net (code "186") (name "/PROG_N") (class "Default")
      (node (ref "J7") (pin "222") (pinfunction "222_222") (pintype "passive"))
    )
    (net (code "187") (name "/RSTI_N") (class "Default")
      (node (ref "J7") (pin "223") (pinfunction "223_223") (pintype "passive"))
    )
    (net (code "188") (name "/VIOREF_R_T") (class "Default")
      (node (ref "J7") (pin "175") (pinfunction "175_175") (pintype "passive"))
      (node (ref "J7") (pin "176") (pinfunction "176_176") (pintype "passive"))
      (node (ref "J7") (pin "178") (pinfunction "178_178") (pintype "passive"))
      (node (ref "J7") (pin "179") (pinfunction "179_179") (pintype "passive"))
      (node (ref "J7") (pin "182") (pinfunction "182_182") (pintype "passive"))
      (node (ref "J7") (pin "183") (pinfunction "183_183") (pintype "passive"))
      (node (ref "J7") (pin "185") (pinfunction "185_185") (pintype "passive"))
      (node (ref "J7") (pin "186") (pinfunction "186_186") (pintype "passive"))
      (node (ref "J7") (pin "188") (pinfunction "188_188") (pintype "passive"))
      (node (ref "J7") (pin "189") (pinfunction "189_189") (pintype "passive"))
      (node (ref "J7") (pin "192") (pinfunction "192_192") (pintype "passive"))
      (node (ref "J7") (pin "193") (pinfunction "193_193") (pintype "passive"))
      (node (ref "J7") (pin "195") (pinfunction "195_195") (pintype "passive"))
      (node (ref "J7") (pin "196") (pinfunction "196_196") (pintype "passive"))
      (node (ref "J7") (pin "198") (pinfunction "198_198") (pintype "passive"))
      (node (ref "J7") (pin "199") (pinfunction "199_199") (pintype "passive"))
    )
    (net (code "189") (name "/VTTREF_R_T") (class "Default")
      (node (ref "J7") (pin "162") (pinfunction "162_162") (pintype "passive"))
      (node (ref "J7") (pin "163") (pinfunction "163_163") (pintype "passive"))
      (node (ref "J7") (pin "165") (pinfunction "165_165") (pintype "passive"))
      (node (ref "J7") (pin "166") (pinfunction "166_166") (pintype "passive"))
      (node (ref "J7") (pin "168") (pinfunction "168_168") (pintype "passive"))
      (node (ref "J7") (pin "169") (pinfunction "169_169") (pintype "passive"))
      (node (ref "J7") (pin "172") (pinfunction "172_172") (pintype "passive"))
      (node (ref "J7") (pin "173") (pinfunction "173_173") (pintype "passive"))
    )
    (net (code "195") (name "V48") (class "Default")
      (node (ref "J7") (pin "225") (pinfunction "225_225") (pintype "passive"))
      (node (ref "J7") (pin "226") (pinfunction "226_226") (pintype "passive"))
      (node (ref "J7") (pin "228") (pinfunction "228_228") (pintype "passive"))
      (node (ref "J7") (pin "229") (pinfunction "229_229") (pintype "passive"))
      (node (ref "J7") (pin "232") (pinfunction "232_232") (pintype "passive"))
      (node (ref "J7") (pin "233") (pinfunction "233_233") (pintype "passive"))
      (node (ref "J7") (pin "235") (pinfunction "235_235") (pintype "passive"))
      (node (ref "J7") (pin "236") (pinfunction "236_236") (pintype "passive"))
      (node (ref "J7") (pin "238") (pinfunction "238_238") (pintype "passive"))
      (node (ref "J7") (pin "239") (pinfunction "239_239") (pintype "passive"))
      (node (ref "J7") (pin "242") (pinfunction "242_242") (pintype "passive"))
      (node (ref "J7") (pin "243") (pinfunction "243_243") (pintype "passive"))
      (node (ref "J7") (pin "245") (pinfunction "245_245") (pintype "passive"))
      (node (ref "J7") (pin "246") (pinfunction "246_246") (pintype "passive"))
      (node (ref "J7") (pin "248") (pinfunction "248_248") (pintype "passive"))
      (node (ref "J7") (pin "249") (pinfunction "249_249") (pintype "passive"))
    )
    (net (code "196") (name "unconnected-(J7-Pad119)") (class "Default")
      (node (ref "J7") (pin "119") (pinfunction "119_119") (pintype "passive+no_connect"))
    )
    (net (code "197") (name "unconnected-(J7-Pad122)") (class "Default")
      (node (ref "J7") (pin "122") (pinfunction "122_122") (pintype "passive+no_connect"))
    )
    (net (code "198") (name "unconnected-(J7-Pad123)") (class "Default")
      (node (ref "J7") (pin "123") (pinfunction "123_123") (pintype "passive+no_connect"))
    )
    (net (code "199") (name "unconnected-(J7-Pad125)") (class "Default")
      (node (ref "J7") (pin "125") (pinfunction "125_125") (pintype "passive+no_connect"))
    )
    (net (code "200") (name "unconnected-(J7-Pad126)") (class "Default")
      (node (ref "J7") (pin "126") (pinfunction "126_126") (pintype "passive+no_connect"))
    )
    (net (code "201") (name "unconnected-(J7-Pad128)") (class "Default")
      (node (ref "J7") (pin "128") (pinfunction "128_128") (pintype "passive+no_connect"))
    )
    (net (code "202") (name "unconnected-(J7-Pad129)") (class "Default")
      (node (ref "J7") (pin "129") (pinfunction "129_129") (pintype "passive+no_connect"))
    )
    (net (code "203") (name "unconnected-(J7-Pad132)") (class "Default")
      (node (ref "J7") (pin "132") (pinfunction "132_132") (pintype "passive+no_connect"))
    )
    (net (code "204") (name "unconnected-(J7-Pad133)") (class "Default")
      (node (ref "J7") (pin "133") (pinfunction "133_133") (pintype "passive+no_connect"))
    )
    (net (code "205") (name "unconnected-(J7-Pad135)") (class "Default")
      (node (ref "J7") (pin "135") (pinfunction "135_135") (pintype "passive+no_connect"))
    )
    (net (code "206") (name "unconnected-(J7-Pad136)") (class "Default")
      (node (ref "J7") (pin "136") (pinfunction "136_136") (pintype "passive+no_connect"))
    )
    (net (code "207") (name "unconnected-(J7-Pad138)") (class "Default")
      (node (ref "J7") (pin "138") (pinfunction "138_138") (pintype "passive+no_connect"))
    )
    (net (code "208") (name "unconnected-(J7-Pad139)") (class "Default")
      (node (ref "J7") (pin "139") (pinfunction "139_139") (pintype "passive+no_connect"))
    )
    (net (code "209") (name "unconnected-(J7-Pad142)") (class "Default")
      (node (ref "J7") (pin "142") (pinfunction "142_142") (pintype "passive+no_connect"))
    )
    (net (code "210") (name "unconnected-(J7-Pad143)") (class "Default")
      (node (ref "J7") (pin "143") (pinfunction "143_143") (pintype "passive+no_connect"))
    )
    (net (code "211") (name "unconnected-(J7-Pad145)") (class "Default")
      (node (ref "J7") (pin "145") (pinfunction "145_145") (pintype "passive+no_connect"))
    )
    (net (code "212") (name "unconnected-(J7-Pad146)") (class "Default")
      (node (ref "J7") (pin "146") (pinfunction "146_146") (pintype "passive+no_connect"))
    )
    (net (code "213") (name "unconnected-(J7-Pad148)") (class "Default")
      (node (ref "J7") (pin "148") (pinfunction "148_148") (pintype "passive+no_connect"))
    )
    (net (code "214") (name "unconnected-(J7-Pad149)") (class "Default")
      (node (ref "J7") (pin "149") (pinfunction "149_149") (pintype "passive+no_connect"))
    )
    (net (code "215") (name "unconnected-(J7-Pad299)") (class "Default")
      (node (ref "J7") (pin "299") (pinfunction "299_299") (pintype "passive+no_connect"))
    )
  )
)
